# CTR-Lower-Main-Board-Rev-B-Sensors-4.net
KiCad netlist of a schematic drawn in Altium Designer
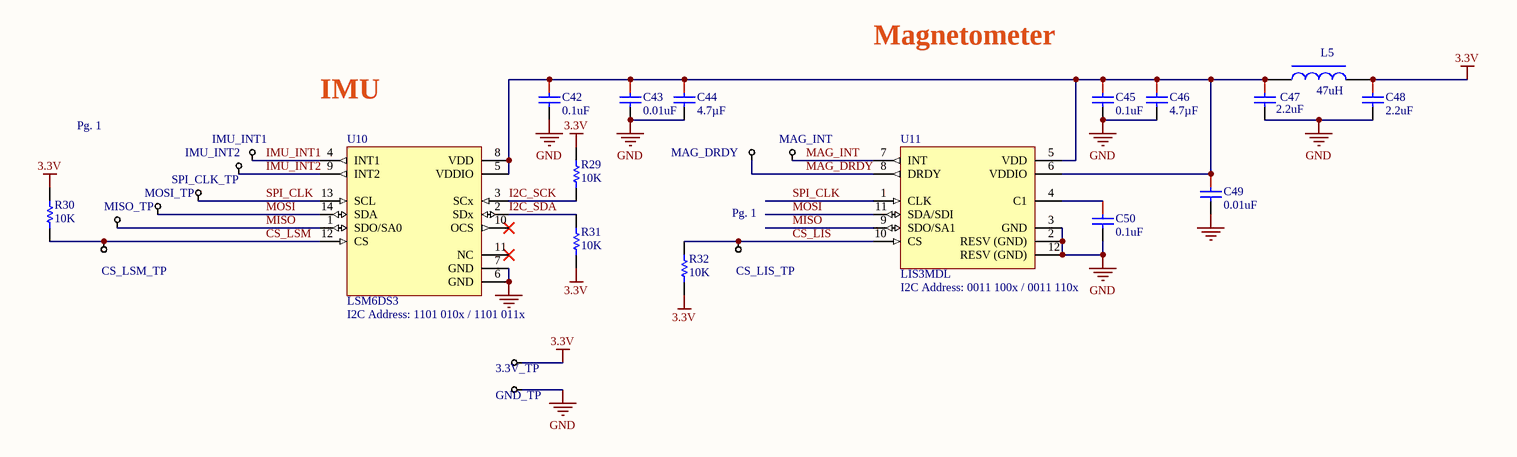
[diagram p0: CTR-Lower-Main-Board-Rev-B-Sensors-4.SchDoc]

(export (version "E")
  (design (tool "Eeschema 10.0.6"))
  (components
    (comp (ref "3.3V_TP")
      (value "3V")
      (footprint "TestPoint-TH 35 mil")
      (description "Test Point")
      (libsource (lib "OLogic-Misc") (part "TestPoint, small"))
    )
    (comp (ref "C42")
      (value "0.1uF")
      (footprint "CAPC0402(1005)_N")
      (description "0.1uF 0402 50V")
      (fields
        (field (name "MANUFACTURER") "TDK Corporation")
        (field (name "MANUFACTURER PART NUMBER") "CGA2B3X7R1H104K050BB")
        (field (name "CREATOR") "osman")
      )
      (libsource (lib "OLogic-Passive") (part "CAP CER 0.1UF 50V 10% X7R 0402"))
    )
    (comp (ref "C43")
      (value "0.01uF")
      (footprint "CAPC0402(1005)_N")
      (description "0.01uF 0402")
      (fields
        (field (name "MANUFACTURER") "Murata Electronics North America")
        (field (name "MANUFACTURER PART NUMBER") "GRM155R71E103KA01D")
      )
      (libsource (lib "OLogic-Passive") (part "CAP CER 0.01UF 25V 10% X5R 0402"))
    )
    (comp (ref "C44")
      (value "4.7UF 0603")
      (footprint "CAPC0603(1608)_L")
      (fields
        (field (name "MANUFACTURER") "Taiyo Yuden")
        (field (name "MANUFACTURER PART NUMBER") "EMK107ABJ475KA-T")
        (field (name "TOLERANCE") "±10%")
        (field (name "CAPACITANCE") "4.7µF")
        (field (name "CREATOR") "osman")
      )
      (libsource (lib "OLogic-Passive") (part "CAP CER 4.7UF 16V 10% X5R 0603"))
    )
    (comp (ref "C45")
      (value "0.1uF")
      (footprint "CAPC0402(1005)_N")
      (description "0.1uF 0402 50V")
      (fields
        (field (name "MANUFACTURER") "TDK Corporation")
        (field (name "MANUFACTURER PART NUMBER") "CGA2B3X7R1H104K050BB")
        (field (name "CREATOR") "osman")
      )
      (libsource (lib "OLogic-Passive") (part "CAP CER 0.1UF 50V 10% X7R 0402"))
    )
    (comp (ref "C46")
      (value "4.7UF 0603")
      (footprint "CAPC0603(1608)_L")
      (fields
        (field (name "MANUFACTURER") "Taiyo Yuden")
        (field (name "MANUFACTURER PART NUMBER") "EMK107ABJ475KA-T")
        (field (name "TOLERANCE") "±10%")
        (field (name "CAPACITANCE") "4.7µF")
        (field (name "CREATOR") "osman")
      )
      (libsource (lib "OLogic-Passive") (part "CAP CER 4.7UF 16V 10% X5R 0603"))
    )
    (comp (ref "C47")
      (value "2.2uF")
      (footprint "CAPC0402(1005)_N")
      (description "2.2uF 0402")
      (fields
        (field (name "MANUFACTURER") "TDK Corporation")
        (field (name "MANUFACTURER PART NUMBER") "C1005X5R1V225K050BC")
        (field (name "CREATOR") "osman")
      )
      (libsource (lib "OLogic-Passive") (part "CAP CER 2.2UF 35V 10% X5R 0402"))
    )
    (comp (ref "C48")
      (value "2.2uF")
      (footprint "CAPC0402(1005)_N")
      (description "2.2uF 0402")
      (fields
        (field (name "MANUFACTURER") "TDK Corporation")
        (field (name "MANUFACTURER PART NUMBER") "C1005X5R1V225K050BC")
        (field (name "CREATOR") "osman")
      )
      (libsource (lib "OLogic-Passive") (part "CAP CER 2.2UF 35V 10% X5R 0402"))
    )
    (comp (ref "C49")
      (value "0.01uF")
      (footprint "CAPC0402(1005)_N")
      (description "0.01uF 0402")
      (fields
        (field (name "MANUFACTURER") "Murata Electronics North America")
        (field (name "MANUFACTURER PART NUMBER") "GRM155R71E103KA01D")
      )
      (libsource (lib "OLogic-Passive") (part "CAP CER 0.01UF 25V 10% X5R 0402"))
    )
    (comp (ref "C50")
      (value "0.1uF")
      (footprint "CAPC0402(1005)_N")
      (description "0.1uF 0402 50V")
      (fields
        (field (name "MANUFACTURER") "TDK Corporation")
        (field (name "MANUFACTURER PART NUMBER") "CGA2B3X7R1H104K050BB")
        (field (name "CREATOR") "osman")
      )
      (libsource (lib "OLogic-Passive") (part "CAP CER 0.1UF 50V 10% X7R 0402"))
    )
    (comp (ref "CS_LIS_TP")
      (value "Test Point")
      (footprint "TestPoint-TH 42 mil")
      (libsource (lib "OLogic-Misc") (part "TestPoint, small"))
    )
    (comp (ref "CS_LSM_TP")
      (value "Test Point")
      (footprint "TestPoint-TH 42 mil")
      (libsource (lib "OLogic-Misc") (part "TestPoint, small"))
    )
    (comp (ref "GND_TP")
      (value "GND")
      (footprint "TestPoint-TH 35 mil")
      (description "Test Point")
      (libsource (lib "OLogic-Misc") (part "TestPoint, small"))
    )
    (comp (ref "IMU_INT1")
      (value "Test Point")
      (footprint "TestPoint-TH 42 mil")
      (libsource (lib "OLogic-Misc") (part "TestPoint, small"))
    )
    (comp (ref "IMU_INT2")
      (value "Test Point")
      (footprint "TestPoint-TH 42 mil")
      (libsource (lib "OLogic-Misc") (part "TestPoint, small"))
    )
    (comp (ref "L5")
      (value "47uH")
      (footprint "IND-2012 Chip")
      (description "47uH 0805")
      (fields
        (field (name "MANUFACTURER") "TDK Corporation")
        (field (name "MANUFACTURER PART NUMBER") "MLZ2012M470WT000")
      )
      (libsource (lib "OLogic-Passive") (part "INDUCTOR MULTILAYER 47UH 100mA 0805"))
    )
    (comp (ref "MAG_DRDY")
      (value "Test Point")
      (footprint "TestPoint-TH 42 mil")
      (libsource (lib "OLogic-Misc") (part "TestPoint, small"))
    )
    (comp (ref "MAG_INT")
      (value "Test Point")
      (footprint "TestPoint-TH 42 mil")
      (libsource (lib "OLogic-Misc") (part "TestPoint, small"))
    )
    (comp (ref "MISO_TP")
      (value "Test Point")
      (footprint "TestPoint-TH 42 mil")
      (libsource (lib "OLogic-Misc") (part "TestPoint, small"))
    )
    (comp (ref "MOSI_TP")
      (value "Test Point")
      (footprint "TestPoint-TH 42 mil")
      (libsource (lib "OLogic-Misc") (part "TestPoint, small"))
    )
    (comp (ref "R29")
      (value "10K")
      (footprint "RESC0402(1005)_N")
      (description "10K 0402")
      (fields
        (field (name "MANUFACTURER") "Panasonic Electronic Components")
        (field (name "MANUFACTURER PART NUMBER") "ERJ-2GEJ103X")
        (field (name "CREATOR") "ted")
      )
      (libsource (lib "OLogic-Passive") (part "RES 10K OHM 5% 1/10W 0402"))
    )
    (comp (ref "R30")
      (value "10K")
      (footprint "RESC0402(1005)_N")
      (description "10K 0402")
      (fields
        (field (name "MANUFACTURER") "Panasonic Electronic Components")
        (field (name "MANUFACTURER PART NUMBER") "ERJ-2GEJ103X")
        (field (name "CREATOR") "ted")
      )
      (libsource (lib "OLogic-Passive") (part "RES 10K OHM 5% 1/10W 0402"))
    )
    (comp (ref "R31")
      (value "10K")
      (footprint "RESC0402(1005)_N")
      (description "10K 0402")
      (fields
        (field (name "MANUFACTURER") "Panasonic Electronic Components")
        (field (name "MANUFACTURER PART NUMBER") "ERJ-2GEJ103X")
        (field (name "CREATOR") "ted")
      )
      (libsource (lib "OLogic-Passive") (part "RES 10K OHM 5% 1/10W 0402"))
    )
    (comp (ref "R32")
      (value "10K")
      (footprint "RESC0402(1005)_N")
      (description "10K 0402")
      (fields
        (field (name "MANUFACTURER") "Panasonic Electronic Components")
        (field (name "MANUFACTURER PART NUMBER") "ERJ-2GEJ103X")
        (field (name "CREATOR") "ted")
      )
      (libsource (lib "OLogic-Passive") (part "RES 10K OHM 5% 1/10W 0402"))
    )
    (comp (ref "SPI_CLK_TP")
      (value "Test Point")
      (footprint "TestPoint-TH 42 mil")
      (libsource (lib "OLogic-Misc") (part "TestPoint, small"))
    )
    (comp (ref "U10")
      (value "LSM6DS3")
      (footprint "LSM6DS3")
      (description "3D ACC/GYRO INEMO 14VFLGA")
      (fields
        (field (name "MANUFACTURER") "STMicroelectronics")
        (field (name "MANUFACTURER PART NUMBER") "LSM6DS3")
        (field (name "I2C ADDRESS") "1101 010x / 1101 011x")
        (field (name "CREATOR") "osman")
      )
      (libsource (lib "OLogic-Sensors") (part "LSM6DS3"))
    )
    (comp (ref "U11")
      (value "LIS3MDL")
      (footprint "LIS3MDL")
      (description "IC MAGNETOMETER 3-AXIS 12LGA")
      (fields
        (field (name "MANUFACTURER") "STMicroelectronics")
        (field (name "MANUFACTURER PART NUMBER") "LIS3MDL")
        (field (name "I2C ADDRESS") "0011 100x / 0011 110x")
        (field (name "CREATOR") "osman")
      )
      (libsource (lib "OLogic-Sensors") (part "LIS3MDL"))
    )
  )
  (nets
    (net (code "1") (name "/CS_LIS") (class "Default")
      (node (ref "CS_LIS_TP") (pin "1") (pinfunction "1_1") (pintype "passive"))
      (node (ref "R32") (pin "2") (pinfunction "2_2") (pintype "passive"))
      (node (ref "U11") (pin "10") (pinfunction "CS_10") (pintype "input"))
    )
    (net (code "2") (name "/CS_LSM") (class "Default")
      (node (ref "CS_LSM_TP") (pin "1") (pinfunction "1_1") (pintype "passive"))
      (node (ref "R30") (pin "1") (pinfunction "1_1") (pintype "passive"))
      (node (ref "U10") (pin "12") (pinfunction "CS_12") (pintype "input"))
    )
    (net (code "3") (name "/I2C_SCK") (class "Default")
      (node (ref "R29") (pin "1") (pinfunction "1_1") (pintype "passive"))
      (node (ref "U10") (pin "3") (pinfunction "SCx_3") (pintype "input"))
    )
    (net (code "4") (name "/I2C_SDA") (class "Default")
      (node (ref "R31") (pin "2") (pinfunction "2_2") (pintype "passive"))
      (node (ref "U10") (pin "2") (pinfunction "SDx_2") (pintype "bidirectional"))
    )
    (net (code "5") (name "/IMU_INT1") (class "Default")
      (node (ref "IMU_INT1") (pin "1") (pinfunction "1_1") (pintype "passive"))
      (node (ref "U10") (pin "4") (pinfunction "INT1_4") (pintype "output"))
    )
    (net (code "6") (name "/IMU_INT2") (class "Default")
      (node (ref "IMU_INT2") (pin "1") (pinfunction "1_1") (pintype "passive"))
      (node (ref "U10") (pin "9") (pinfunction "INT2_9") (pintype "output"))
    )
    (net (code "7") (name "/MAG_DRDY") (class "Default")
      (node (ref "MAG_DRDY") (pin "1") (pinfunction "1_1") (pintype "passive"))
      (node (ref "U11") (pin "8") (pinfunction "DRDY_8") (pintype "output"))
    )
    (net (code "8") (name "/MAG_INT") (class "Default")
      (node (ref "MAG_INT") (pin "1") (pinfunction "1_1") (pintype "passive"))
      (node (ref "U11") (pin "7") (pinfunction "INT_7") (pintype "output"))
    )
    (net (code "9") (name "/MISO") (class "Default")
      (node (ref "MISO_TP") (pin "1") (pinfunction "1_1") (pintype "passive"))
      (node (ref "U10") (pin "1") (pinfunction "SDO/SA0_1") (pintype "bidirectional"))
      (node (ref "U11") (pin "9") (pinfunction "SDO/SA1_9") (pintype "bidirectional"))
    )
    (net (code "10") (name "/MOSI") (class "Default")
      (node (ref "MOSI_TP") (pin "1") (pinfunction "1_1") (pintype "passive"))
      (node (ref "U10") (pin "14") (pinfunction "SDA_14") (pintype "bidirectional"))
      (node (ref "U11") (pin "11") (pinfunction "SDA/SDI_11") (pintype "bidirectional"))
    )
    (net (code "11") (name "/SPI_CLK") (class "Default")
      (node (ref "SPI_CLK_TP") (pin "1") (pinfunction "1_1") (pintype "passive"))
      (node (ref "U10") (pin "13") (pinfunction "SCL_13") (pintype "input"))
      (node (ref "U11") (pin "1") (pinfunction "CLK_1") (pintype "input"))
    )
    (net (code "12") (name "3.3V") (class "Default")
      (node (ref "3.3V_TP") (pin "1") (pinfunction "1_1") (pintype "passive"))
      (node (ref "C48") (pin "1") (pinfunction "1_1") (pintype "passive"))
      (node (ref "L5") (pin "2") (pinfunction "2_2") (pintype "passive"))
      (node (ref "R29") (pin "2") (pinfunction "2_2") (pintype "passive"))
      (node (ref "R30") (pin "2") (pinfunction "2_2") (pintype "passive"))
      (node (ref "R31") (pin "1") (pinfunction "1_1") (pintype "passive"))
      (node (ref "R32") (pin "1") (pinfunction "1_1") (pintype "passive"))
    )
    (net (code "13") (name "GND") (class "Default")
      (node (ref "C42") (pin "2") (pinfunction "2_2") (pintype "passive"))
      (node (ref "C43") (pin "2") (pinfunction "2_2") (pintype "passive"))
      (node (ref "C44") (pin "2") (pinfunction "2_2") (pintype "passive"))
      (node (ref "C45") (pin "2") (pinfunction "2_2") (pintype "passive"))
      (node (ref "C46") (pin "2") (pinfunction "2_2") (pintype "passive"))
      (node (ref "C47") (pin "2") (pinfunction "2_2") (pintype "passive"))
      (node (ref "C48") (pin "2") (pinfunction "2_2") (pintype "passive"))
      (node (ref "C49") (pin "2") (pinfunction "2_2") (pintype "passive"))
      (node (ref "C50") (pin "2") (pinfunction "2_2") (pintype "passive"))
      (node (ref "GND_TP") (pin "1") (pinfunction "1_1") (pintype "passive"))
      (node (ref "U10") (pin "6") (pinfunction "GND_6") (pintype "power_in"))
      (node (ref "U10") (pin "7") (pinfunction "GND_7") (pintype "power_in"))
      (node (ref "U11") (pin "12") (pinfunction "RESV_(GND)_12") (pintype "power_in"))
      (node (ref "U11") (pin "2") (pinfunction "RESV_(GND)_2") (pintype "power_in"))
      (node (ref "U11") (pin "3") (pinfunction "GND_3") (pintype "power_in"))
    )
    (net (code "14") (name "Net-(U10-VDD)") (class "Default")
      (node (ref "C42") (pin "1") (pinfunction "1_1") (pintype "passive"))
      (node (ref "C43") (pin "1") (pinfunction "1_1") (pintype "passive"))
      (node (ref "C44") (pin "1") (pinfunction "1_1") (pintype "passive"))
      (node (ref "C45") (pin "1") (pinfunction "1_1") (pintype "passive"))
      (node (ref "C46") (pin "1") (pinfunction "1_1") (pintype "passive"))
      (node (ref "C47") (pin "1") (pinfunction "1_1") (pintype "passive"))
      (node (ref "C49") (pin "1") (pinfunction "1_1") (pintype "passive"))
      (node (ref "L5") (pin "1") (pinfunction "1_1") (pintype "passive"))
      (node (ref "U10") (pin "5") (pinfunction "VDDIO_5") (pintype "power_in"))
      (node (ref "U10") (pin "8") (pinfunction "VDD_8") (pintype "power_in"))
      (node (ref "U11") (pin "5") (pinfunction "VDD_5") (pintype "power_in"))
      (node (ref "U11") (pin "6") (pinfunction "VDDIO_6") (pintype "power_in"))
    )
    (net (code "15") (name "Net-(U11-C1)") (class "Default")
      (node (ref "C50") (pin "1") (pinfunction "1_1") (pintype "passive"))
      (node (ref "U11") (pin "4") (pinfunction "C1_4") (pintype "power_in"))
    )
    (net (code "16") (name "unconnected-(U10-NC-Pad11)") (class "Default")
      (node (ref "U10") (pin "11") (pinfunction "NC_11") (pintype "passive+no_connect"))
    )
    (net (code "17") (name "unconnected-(U10-OCS-Pad10)") (class "Default")
      (node (ref "U10") (pin "10") (pinfunction "OCS_10") (pintype "output+no_connect"))
    )
  )
)
